# HDMI_Input.net
KiCad netlist of a schematic drawn in Altium Designer
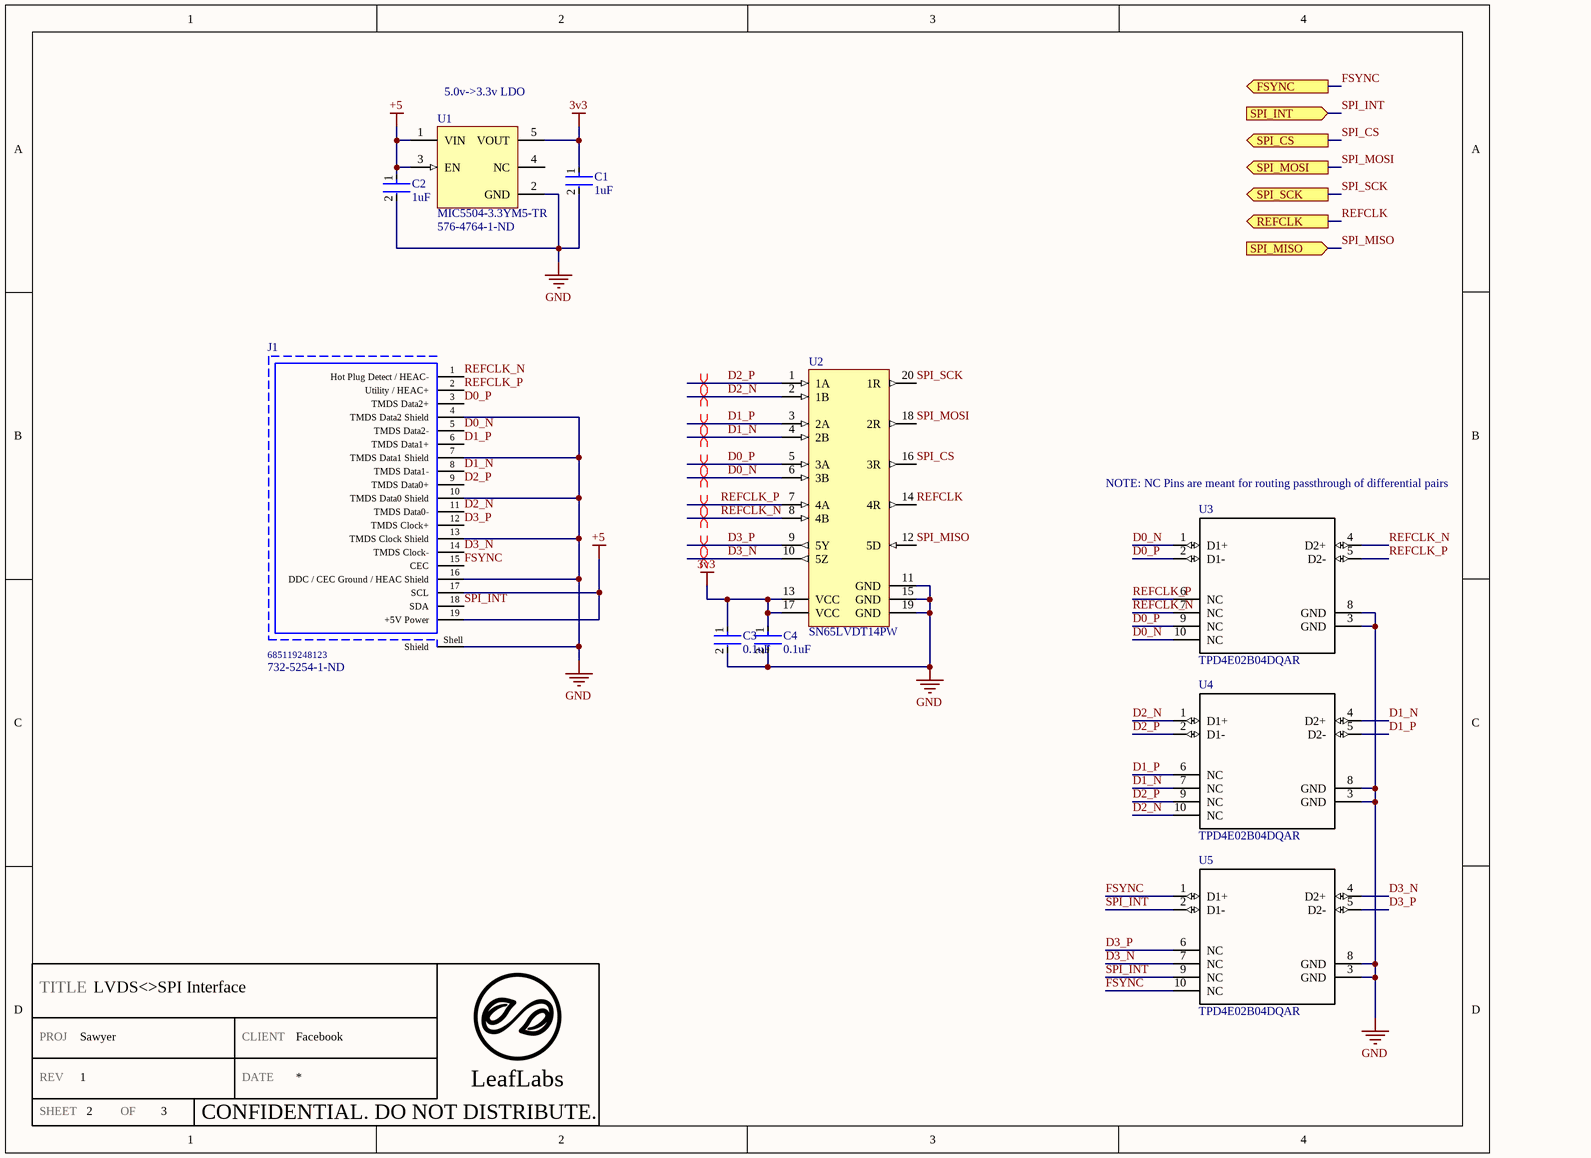
[diagram p0: HDMI_Input.SchDoc]

(export (version "E")
  (design (tool "Eeschema 10.0.6"))
  (components
    (comp (ref "C1")
      (value "1uF")
      (footprint "FP-CC0603-DA-IPC_B")
      (description "CAP CER 1UF X7R 0603")
      (libsource (lib "Capacitors") (part "CAP-0603-1uF"))
    )
    (comp (ref "C2")
      (value "1uF")
      (footprint "FP-CC0603-DA-IPC_B")
      (description "CAP CER 1UF X7R 0603")
      (libsource (lib "Capacitors") (part "CAP-0603-1uF"))
    )
    (comp (ref "C3")
      (value "0.1uF")
      (footprint "FP-CC0603-DA-IPC_C")
      (description "CAP CER 0.1UF 16V X7R 0603")
      (fields
        (field (name "OCTOPART") "https://octopart.com/cc0603krx7r7bb104-yageo-192941")
        (field (name "TOLERANCE") "0.1")
      )
      (libsource (lib "LeafLabs_Commercial") (part "CAP-0603-0.1uF"))
    )
    (comp (ref "C4")
      (value "0.1uF")
      (footprint "FP-CC0603-DA-IPC_C")
      (description "CAP CER 0.1UF 16V X7R 0603")
      (fields
        (field (name "OCTOPART") "https://octopart.com/cc0603krx7r7bb104-yageo-192941")
        (field (name "TOLERANCE") "0.1")
      )
      (libsource (lib "LeafLabs_Commercial") (part "CAP-0603-0.1uF"))
    )
    (comp (ref "J1")
      (value "685119248123")
      (footprint "685119248123")
      (description "Micro HDMI Type D Receptacle WR-COM, Horizontal, SMT")
      (fields
        (field (name "MANUFACTURER") "Wurth Elektronik")
        (field (name "SUPPLIER PART NUMBER 1") "732-5254-1-ND")
        (field (name "PUBLISHER") "WurthElektronik")
      )
      (libsource (lib "Connectors") (part "685119248123"))
    )
    (comp (ref "U1")
      (value "MIC5504-3.3YM5-TR")
      (footprint "SOT-23-M5_V")
      (fields
        (field (name "MANUFACTURER") "Microchip")
        (field (name "SUPPLIER PART NUMBER 1") "576-4764-1-ND")
      )
      (libsource (lib "LeafLabs_Commercial") (part "MIC5504-3.3YM5-TR"))
    )
    (comp (ref "U2")
      (value "SN65LVDT14PW")
      (footprint "PW0020A_L")
      (description "SPI<>LVDS Transceiver, 1 Tx and 4 Rx, -55 to +125 degC, 20-pin TSSOP (PW), Green (RoHS & no Sb/Br)")
      (fields (field (name "MANUFACTURER") "Texas Instruments"))
      (libsource (lib "Transceivers") (part "SN65LVDT14PW"))
    )
    (comp (ref "U3")
      (value "TPD4E02B04DQAR")
      (footprint "DQA0010A")
      (description "4 Channel TVS Avalanch diode for USB3/HDMI2.0 protection")
      (fields
        (field (name "MANUFACTURER") "Texas Instruments")
        (field (name "COPYRIGHT") "Copyright (C) 2018 Accelerated Designs. All rights reserved")
      )
      (libsource (lib "LeafLabs_Commercial") (part "TPD4E02B04DQAR"))
    )
    (comp (ref "U4")
      (value "TPD4E02B04DQAR")
      (footprint "DQA0010A")
      (description "4 Channel TVS Avalanch diode for USB3/HDMI2.0 protection")
      (fields
        (field (name "MANUFACTURER") "Texas Instruments")
        (field (name "COPYRIGHT") "Copyright (C) 2018 Accelerated Designs. All rights reserved")
      )
      (libsource (lib "LeafLabs_Commercial") (part "TPD4E02B04DQAR"))
    )
    (comp (ref "U5")
      (value "TPD4E02B04DQAR")
      (footprint "DQA0010A")
      (description "4 Channel TVS Avalanch diode for USB3/HDMI2.0 protection")
      (fields
        (field (name "MANUFACTURER") "Texas Instruments")
        (field (name "COPYRIGHT") "Copyright (C) 2018 Accelerated Designs. All rights reserved")
      )
      (libsource (lib "LeafLabs_Commercial") (part "TPD4E02B04DQAR"))
    )
  )
  (nets
    (net (code "1") (name "+5") (class "Default")
      (node (ref "C2") (pin "1") (pinfunction "1_1") (pintype "passive"))
      (node (ref "J1") (pin "17") (pinfunction "SCL_17") (pintype "passive"))
      (node (ref "J1") (pin "19") (pinfunction "+5V_Power_19") (pintype "passive"))
      (node (ref "U1") (pin "1") (pinfunction "VIN_1") (pintype "power_in"))
      (node (ref "U1") (pin "3") (pinfunction "EN_3") (pintype "input"))
    )
    (net (code "2") (name "/D0_N") (class "Default")
      (node (ref "J1") (pin "5") (pinfunction "TMDS_Data2-_5") (pintype "passive"))
      (node (ref "U2") (pin "6") (pinfunction "3B_6") (pintype "input"))
      (node (ref "U3") (pin "1") (pinfunction "D1+_1") (pintype "bidirectional"))
      (node (ref "U3") (pin "10") (pinfunction "NC_10") (pintype "passive"))
    )
    (net (code "3") (name "/D0_P") (class "Default")
      (node (ref "J1") (pin "3") (pinfunction "TMDS_Data2+_3") (pintype "passive"))
      (node (ref "U2") (pin "5") (pinfunction "3A_5") (pintype "input"))
      (node (ref "U3") (pin "2") (pinfunction "D1-_2") (pintype "bidirectional"))
      (node (ref "U3") (pin "9") (pinfunction "NC_9") (pintype "passive"))
    )
    (net (code "4") (name "/D1_N") (class "Default")
      (node (ref "J1") (pin "8") (pinfunction "TMDS_Data1-_8") (pintype "passive"))
      (node (ref "U2") (pin "4") (pinfunction "2B_4") (pintype "input"))
      (node (ref "U4") (pin "4") (pinfunction "D2+_4") (pintype "bidirectional"))
      (node (ref "U4") (pin "7") (pinfunction "NC_7") (pintype "passive"))
    )
    (net (code "5") (name "/D1_P") (class "Default")
      (node (ref "J1") (pin "6") (pinfunction "TMDS_Data1+_6") (pintype "passive"))
      (node (ref "U2") (pin "3") (pinfunction "2A_3") (pintype "input"))
      (node (ref "U4") (pin "5") (pinfunction "D2-_5") (pintype "bidirectional"))
      (node (ref "U4") (pin "6") (pinfunction "NC_6") (pintype "passive"))
    )
    (net (code "6") (name "/D2_N") (class "Default")
      (node (ref "J1") (pin "11") (pinfunction "TMDS_Data0-_11") (pintype "passive"))
      (node (ref "U2") (pin "2") (pinfunction "1B_2") (pintype "input"))
      (node (ref "U4") (pin "1") (pinfunction "D1+_1") (pintype "bidirectional"))
      (node (ref "U4") (pin "10") (pinfunction "NC_10") (pintype "passive"))
    )
    (net (code "7") (name "/D2_P") (class "Default")
      (node (ref "J1") (pin "9") (pinfunction "TMDS_Data0+_9") (pintype "passive"))
      (node (ref "U2") (pin "1") (pinfunction "1A_1") (pintype "input"))
      (node (ref "U4") (pin "2") (pinfunction "D1-_2") (pintype "bidirectional"))
      (node (ref "U4") (pin "9") (pinfunction "NC_9") (pintype "passive"))
    )
    (net (code "8") (name "/D3_N") (class "Default")
      (node (ref "J1") (pin "14") (pinfunction "TMDS_Clock-_14") (pintype "passive"))
      (node (ref "U2") (pin "10") (pinfunction "5Z_10") (pintype "output"))
      (node (ref "U5") (pin "4") (pinfunction "D2+_4") (pintype "bidirectional"))
      (node (ref "U5") (pin "7") (pinfunction "NC_7") (pintype "passive"))
    )
    (net (code "9") (name "/D3_P") (class "Default")
      (node (ref "J1") (pin "12") (pinfunction "TMDS_Clock+_12") (pintype "passive"))
      (node (ref "U2") (pin "9") (pinfunction "5Y_9") (pintype "output"))
      (node (ref "U5") (pin "5") (pinfunction "D2-_5") (pintype "bidirectional"))
      (node (ref "U5") (pin "6") (pinfunction "NC_6") (pintype "passive"))
    )
    (net (code "10") (name "/FSYNC") (class "Default")
      (node (ref "J1") (pin "15") (pinfunction "CEC_15") (pintype "passive"))
      (node (ref "U5") (pin "1") (pinfunction "D1+_1") (pintype "bidirectional"))
      (node (ref "U5") (pin "10") (pinfunction "NC_10") (pintype "passive"))
    )
    (net (code "11") (name "/REFCLK") (class "Default")
      (node (ref "U2") (pin "14") (pinfunction "4R_14") (pintype "output"))
    )
    (net (code "12") (name "/REFCLK_N") (class "Default")
      (node (ref "J1") (pin "1") (pinfunction "Hot_Plug_Detect_/_HEAC-_1") (pintype "passive"))
      (node (ref "U2") (pin "8") (pinfunction "4B_8") (pintype "input"))
      (node (ref "U3") (pin "4") (pinfunction "D2+_4") (pintype "bidirectional"))
      (node (ref "U3") (pin "7") (pinfunction "NC_7") (pintype "passive"))
    )
    (net (code "13") (name "/REFCLK_P") (class "Default")
      (node (ref "J1") (pin "2") (pinfunction "Utility_/_HEAC+_2") (pintype "passive"))
      (node (ref "U2") (pin "7") (pinfunction "4A_7") (pintype "input"))
      (node (ref "U3") (pin "5") (pinfunction "D2-_5") (pintype "bidirectional"))
      (node (ref "U3") (pin "6") (pinfunction "NC_6") (pintype "passive"))
    )
    (net (code "14") (name "/SPI_CS") (class "Default")
      (node (ref "U2") (pin "16") (pinfunction "3R_16") (pintype "output"))
    )
    (net (code "15") (name "/SPI_INT") (class "Default")
      (node (ref "J1") (pin "18") (pinfunction "SDA_18") (pintype "passive"))
      (node (ref "U5") (pin "2") (pinfunction "D1-_2") (pintype "bidirectional"))
      (node (ref "U5") (pin "9") (pinfunction "NC_9") (pintype "passive"))
    )
    (net (code "16") (name "/SPI_MISO") (class "Default")
      (node (ref "U2") (pin "12") (pinfunction "5D_12") (pintype "input"))
    )
    (net (code "17") (name "/SPI_MOSI") (class "Default")
      (node (ref "U2") (pin "18") (pinfunction "2R_18") (pintype "output"))
    )
    (net (code "18") (name "/SPI_SCK") (class "Default")
      (node (ref "U2") (pin "20") (pinfunction "1R_20") (pintype "output"))
    )
    (net (code "19") (name "3v3") (class "Default")
      (node (ref "C1") (pin "1") (pinfunction "1_1") (pintype "passive"))
      (node (ref "C3") (pin "1") (pinfunction "1_1") (pintype "passive"))
      (node (ref "C4") (pin "1") (pinfunction "1_1") (pintype "passive"))
      (node (ref "U1") (pin "5") (pinfunction "VOUT_5") (pintype "power_in"))
      (node (ref "U2") (pin "13") (pinfunction "VCC_13") (pintype "power_in"))
      (node (ref "U2") (pin "17") (pinfunction "VCC_17") (pintype "power_in"))
    )
    (net (code "20") (name "GND") (class "Default")
      (node (ref "C1") (pin "2") (pinfunction "2_2") (pintype "passive"))
      (node (ref "C2") (pin "2") (pinfunction "2_2") (pintype "passive"))
      (node (ref "C3") (pin "2") (pinfunction "2_2") (pintype "passive"))
      (node (ref "C4") (pin "2") (pinfunction "2_2") (pintype "passive"))
      (node (ref "J1") (pin "10") (pinfunction "TMDS_Data0_Shield_10") (pintype "passive"))
      (node (ref "J1") (pin "13") (pinfunction "TMDS_Clock_Shield_13") (pintype "passive"))
      (node (ref "J1") (pin "16") (pinfunction "DDC_/_CEC_Ground_/_HEAC_Shield_16") (pintype "passive"))
      (node (ref "J1") (pin "4") (pinfunction "TMDS_Data2_Shield_4") (pintype "passive"))
      (node (ref "J1") (pin "7") (pinfunction "TMDS_Data1_Shield_7") (pintype "passive"))
      (node (ref "J1") (pin "Shell") (pinfunction "Shield_Shell") (pintype "passive"))
      (node (ref "U1") (pin "2") (pinfunction "GND_2") (pintype "power_in"))
      (node (ref "U2") (pin "11") (pinfunction "GND_11") (pintype "power_in"))
      (node (ref "U2") (pin "15") (pinfunction "GND_15") (pintype "power_in"))
      (node (ref "U2") (pin "19") (pinfunction "GND_19") (pintype "power_in"))
      (node (ref "U3") (pin "3") (pinfunction "GND_3") (pintype "power_in"))
      (node (ref "U3") (pin "8") (pinfunction "GND_8") (pintype "power_in"))
      (node (ref "U4") (pin "3") (pinfunction "GND_3") (pintype "power_in"))
      (node (ref "U4") (pin "8") (pinfunction "GND_8") (pintype "power_in"))
      (node (ref "U5") (pin "3") (pinfunction "GND_3") (pintype "power_in"))
      (node (ref "U5") (pin "8") (pinfunction "GND_8") (pintype "power_in"))
    )
    (net (code "21") (name "unconnected-(U1-NC-Pad4)") (class "Default")
      (node (ref "U1") (pin "4") (pinfunction "NC_4") (pintype "passive"))
    )
  )
)
